# Servo_Board.net
KiCad netlist of a schematic drawn in EAGLE
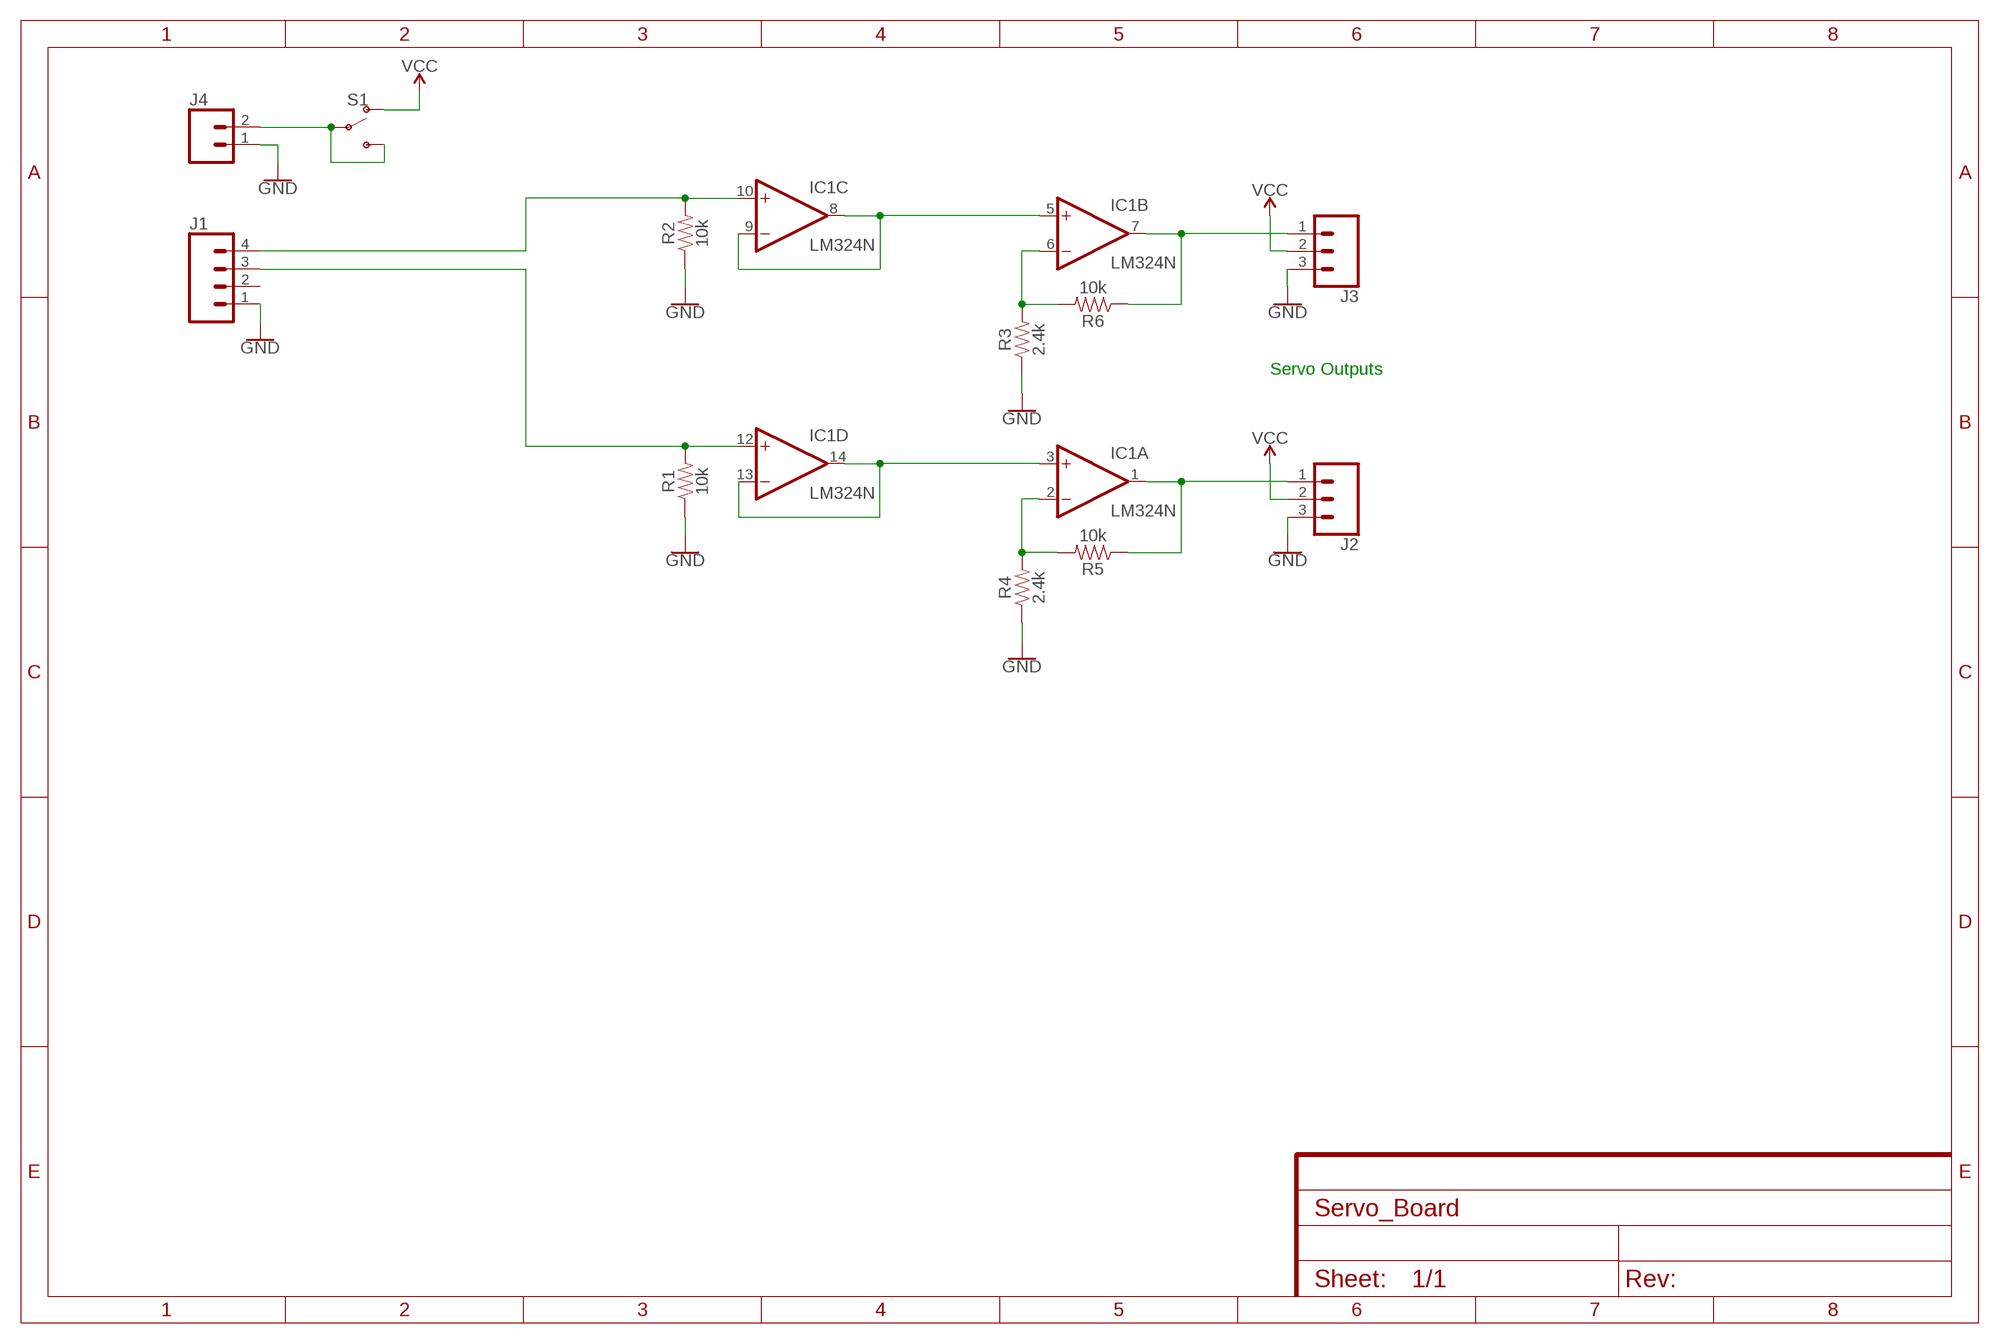
[diagram p0: schematic, sheet 1]

(export (version "E")
  (design (tool "Eeschema 10.0.6"))
  (components
    (comp (ref "IC1")
      (value "LM324N")
      (footprint "eagle-import:DIL14")
      (libsource (lib "eagle-import") (part "LM324N"))
    )
    (comp (ref "J1")
      (value "CONN_04")
      (footprint "eagle-import:1X04")
      (libsource (lib "eagle-import") (part "CONN_04"))
    )
    (comp (ref "J2")
      (value "CONN_03")
      (footprint "eagle-import:1X03")
      (libsource (lib "eagle-import") (part "CONN_03"))
    )
    (comp (ref "J3")
      (value "CONN_03")
      (footprint "eagle-import:1X03")
      (libsource (lib "eagle-import") (part "CONN_03"))
    )
    (comp (ref "J4")
      (value "CONN_02")
      (footprint "eagle-import:1X02")
      (libsource (lib "eagle-import") (part "CONN_02"))
    )
    (comp (ref "R1")
      (value "10k")
      (footprint "eagle-import:AXIAL-0.3")
      (libsource (lib "eagle-import") (part "10KOHM-HORIZ-1/4W-1%"))
    )
    (comp (ref "R2")
      (value "10k")
      (footprint "eagle-import:AXIAL-0.3")
      (libsource (lib "eagle-import") (part "10KOHM-HORIZ-1/4W-1%"))
    )
    (comp (ref "R3")
      (value "2.4k")
      (footprint "eagle-import:AXIAL-0.3")
      (libsource (lib "eagle-import") (part "10KOHM-HORIZ-1/4W-1%"))
    )
    (comp (ref "R4")
      (value "2.4k")
      (footprint "eagle-import:AXIAL-0.3")
      (libsource (lib "eagle-import") (part "10KOHM-HORIZ-1/4W-1%"))
    )
    (comp (ref "R5")
      (value "10k")
      (footprint "eagle-import:AXIAL-0.3")
      (libsource (lib "eagle-import") (part "10KOHM-HORIZ-1/4W-1%"))
    )
    (comp (ref "R6")
      (value "10k")
      (footprint "eagle-import:AXIAL-0.3")
      (libsource (lib "eagle-import") (part "10KOHM-HORIZ-1/4W-1%"))
    )
    (comp (ref "S1")
      (value "SWITCH-SPDT-PTH-11.6X4.0MM")
      (footprint "eagle-import:SWITCH_SPDT_PTH_11.6X4.0MM")
      (libsource (lib "eagle-import") (part "SWITCH-SPDT-PTH-11.6X4.0MM"))
    )
  )
  (nets
    (net (code "1") (name "GND") (class "Default")
      (node (ref "J1") (pin "1") (pinfunction "1_1") (pintype "passive"))
      (node (ref "J2") (pin "3") (pinfunction "3_3") (pintype "passive"))
      (node (ref "J3") (pin "3") (pinfunction "3_3") (pintype "passive"))
      (node (ref "J4") (pin "1") (pinfunction "1_1") (pintype "passive"))
      (node (ref "R1") (pin "P$1") (pinfunction "1_P$1") (pintype "passive"))
      (node (ref "R2") (pin "P$1") (pinfunction "1_P$1") (pintype "passive"))
      (node (ref "R3") (pin "P$1") (pinfunction "1_P$1") (pintype "passive"))
      (node (ref "R4") (pin "P$1") (pinfunction "1_P$1") (pintype "passive"))
    )
    (net (code "2") (name "Net-(IC1A-+IN)") (class "Default")
      (node (ref "IC1") (pin "13") (pinfunction "-IN_13") (pintype "input"))
      (node (ref "IC1") (pin "14") (pinfunction "OUT_14") (pintype "output"))
      (node (ref "IC1") (pin "3") (pinfunction "+IN_3") (pintype "input"))
    )
    (net (code "3") (name "Net-(IC1A--IN)") (class "Default")
      (node (ref "IC1") (pin "2") (pinfunction "-IN_2") (pintype "input"))
      (node (ref "R4") (pin "P$2") (pinfunction "2_P$2") (pintype "passive"))
      (node (ref "R5") (pin "P$2") (pinfunction "2_P$2") (pintype "passive"))
    )
    (net (code "4") (name "Net-(IC1A-OUT)") (class "Default")
      (node (ref "IC1") (pin "1") (pinfunction "OUT_1") (pintype "output"))
      (node (ref "J2") (pin "1") (pinfunction "1_1") (pintype "passive"))
      (node (ref "R5") (pin "P$1") (pinfunction "1_P$1") (pintype "passive"))
    )
    (net (code "5") (name "Net-(IC1B-+IN)") (class "Default")
      (node (ref "IC1") (pin "5") (pinfunction "+IN_5") (pintype "input"))
      (node (ref "IC1") (pin "8") (pinfunction "OUT_8") (pintype "output"))
      (node (ref "IC1") (pin "9") (pinfunction "-IN_9") (pintype "input"))
    )
    (net (code "6") (name "Net-(IC1B--IN)") (class "Default")
      (node (ref "IC1") (pin "6") (pinfunction "-IN_6") (pintype "input"))
      (node (ref "R3") (pin "P$2") (pinfunction "2_P$2") (pintype "passive"))
      (node (ref "R6") (pin "P$2") (pinfunction "2_P$2") (pintype "passive"))
    )
    (net (code "7") (name "Net-(IC1B-OUT)") (class "Default")
      (node (ref "IC1") (pin "7") (pinfunction "OUT_7") (pintype "output"))
      (node (ref "J3") (pin "1") (pinfunction "1_1") (pintype "passive"))
      (node (ref "R6") (pin "P$1") (pinfunction "1_P$1") (pintype "passive"))
    )
    (net (code "8") (name "Net-(IC1C-+IN)") (class "Default")
      (node (ref "IC1") (pin "10") (pinfunction "+IN_10") (pintype "input"))
      (node (ref "J1") (pin "4") (pinfunction "4_4") (pintype "passive"))
      (node (ref "R2") (pin "P$2") (pinfunction "2_P$2") (pintype "passive"))
    )
    (net (code "9") (name "Net-(IC1D-+IN)") (class "Default")
      (node (ref "IC1") (pin "12") (pinfunction "+IN_12") (pintype "input"))
      (node (ref "J1") (pin "3") (pinfunction "3_3") (pintype "passive"))
      (node (ref "R1") (pin "P$2") (pinfunction "2_P$2") (pintype "passive"))
    )
    (net (code "10") (name "Net-(S1-P)") (class "Default")
      (node (ref "J4") (pin "2") (pinfunction "2_2") (pintype "passive"))
      (node (ref "S1") (pin "2") (pinfunction "P_2") (pintype "passive"))
      (node (ref "S1") (pin "3") (pinfunction "S_3") (pintype "passive"))
    )
    (net (code "11") (name "VCC") (class "Default")
      (node (ref "J2") (pin "2") (pinfunction "2_2") (pintype "passive"))
      (node (ref "J3") (pin "2") (pinfunction "2_2") (pintype "passive"))
      (node (ref "S1") (pin "1") (pinfunction "O_1") (pintype "passive"))
    )
    (net (code "12") (name "unconnected-(J1-Pad2)") (class "Default")
      (node (ref "J1") (pin "2") (pinfunction "2_2") (pintype "passive"))
    )
  )
)
